# piezo-layer_v0_1-R003.net
KiCad netlist of a schematic drawn in EAGLE
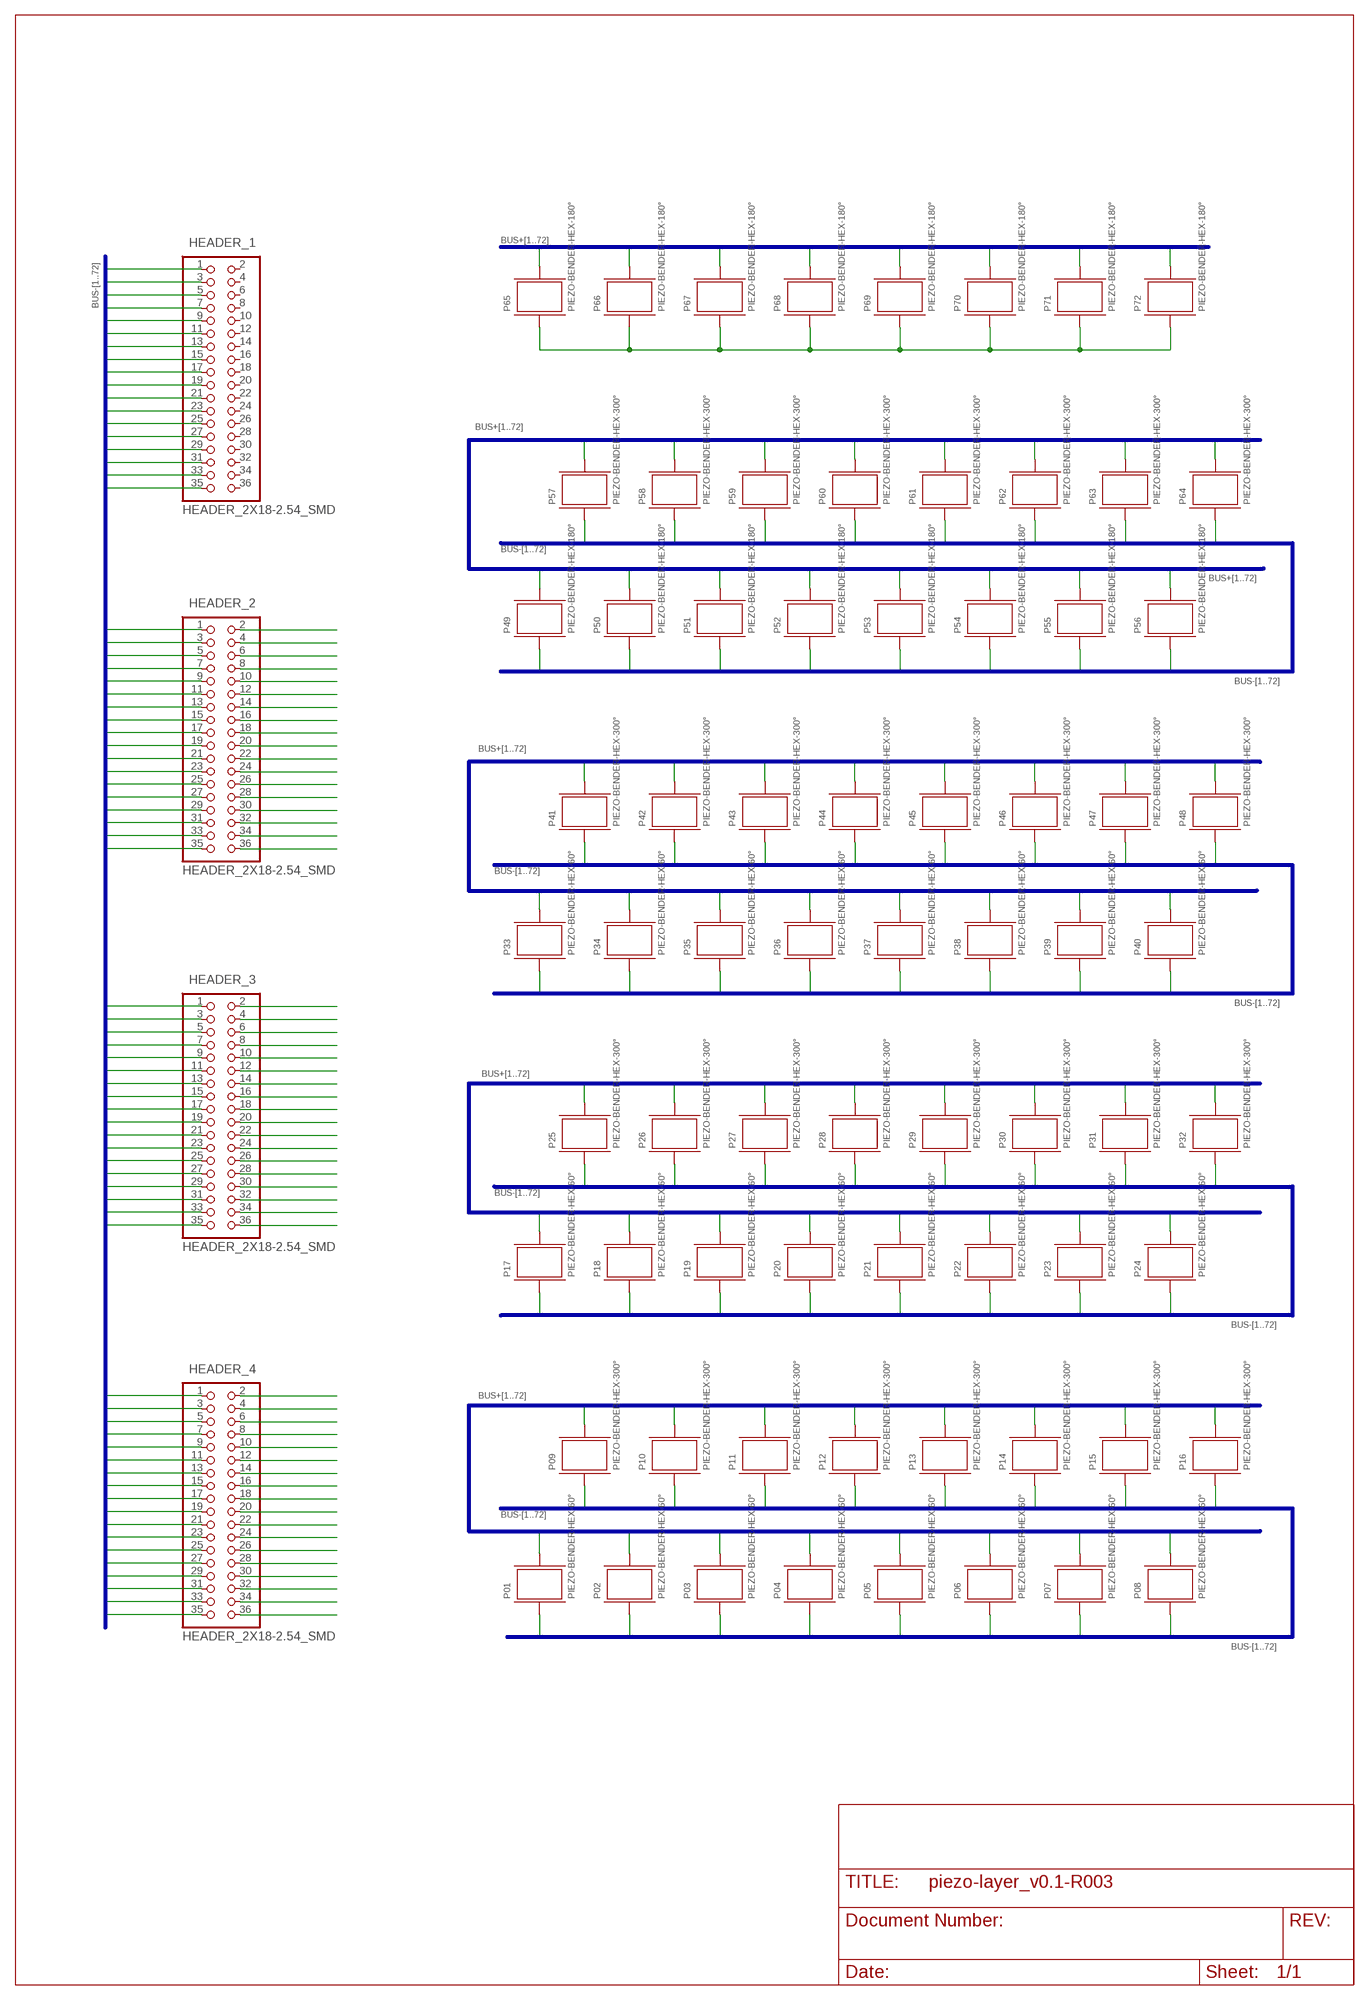
[diagram p0: schematic, sheet 1]

(export (version "E")
  (design (tool "Eeschema 10.0.6"))
  (components
    (comp (ref "HEADER_1")
      (value "HEADER_2X18-2.54_SMD")
      (footprint "eagle-import:2X18_2.54_SMD")
      (libsource (lib "eagle-import") (part "HEADER_2X18-2.54_SMD"))
    )
    (comp (ref "HEADER_2")
      (value "HEADER_2X18-2.54_SMD")
      (footprint "eagle-import:2X18_2.54_SMD")
      (libsource (lib "eagle-import") (part "HEADER_2X18-2.54_SMD"))
    )
    (comp (ref "HEADER_3")
      (value "HEADER_2X18-2.54_SMD")
      (footprint "eagle-import:2X18_2.54_SMD")
      (libsource (lib "eagle-import") (part "HEADER_2X18-2.54_SMD"))
    )
    (comp (ref "HEADER_4")
      (value "HEADER_2X18-2.54_SMD")
      (footprint "eagle-import:2X18_2.54_SMD")
      (libsource (lib "eagle-import") (part "HEADER_2X18-2.54_SMD"))
    )
    (comp (ref "P01")
      (value "PIEZO-BENDER-HEX-60°")
      (footprint "eagle-import:PIEZO-BENDER-HEX_16MM_60°")
      (libsource (lib "eagle-import") (part "PIEZO-BENDER-HEX-60°"))
    )
    (comp (ref "P02")
      (value "PIEZO-BENDER-HEX-60°")
      (footprint "eagle-import:PIEZO-BENDER-HEX_16MM_60°")
      (libsource (lib "eagle-import") (part "PIEZO-BENDER-HEX-60°"))
    )
    (comp (ref "P03")
      (value "PIEZO-BENDER-HEX-60°")
      (footprint "eagle-import:PIEZO-BENDER-HEX_16MM_60°")
      (libsource (lib "eagle-import") (part "PIEZO-BENDER-HEX-60°"))
    )
    (comp (ref "P04")
      (value "PIEZO-BENDER-HEX-60°")
      (footprint "eagle-import:PIEZO-BENDER-HEX_16MM_60°")
      (libsource (lib "eagle-import") (part "PIEZO-BENDER-HEX-60°"))
    )
    (comp (ref "P05")
      (value "PIEZO-BENDER-HEX-60°")
      (footprint "eagle-import:PIEZO-BENDER-HEX_16MM_60°")
      (libsource (lib "eagle-import") (part "PIEZO-BENDER-HEX-60°"))
    )
    (comp (ref "P06")
      (value "PIEZO-BENDER-HEX-60°")
      (footprint "eagle-import:PIEZO-BENDER-HEX_16MM_60°")
      (libsource (lib "eagle-import") (part "PIEZO-BENDER-HEX-60°"))
    )
    (comp (ref "P07")
      (value "PIEZO-BENDER-HEX-60°")
      (footprint "eagle-import:PIEZO-BENDER-HEX_16MM_60°")
      (libsource (lib "eagle-import") (part "PIEZO-BENDER-HEX-60°"))
    )
    (comp (ref "P08")
      (value "PIEZO-BENDER-HEX-60°")
      (footprint "eagle-import:PIEZO-BENDER-HEX_16MM_60°")
      (libsource (lib "eagle-import") (part "PIEZO-BENDER-HEX-60°"))
    )
    (comp (ref "P09")
      (value "PIEZO-BENDER-HEX-300°")
      (footprint "eagle-import:PIEZO-BENDER-HEX_16MM_300°")
      (libsource (lib "eagle-import") (part "PIEZO-BENDER-HEX-300°"))
    )
    (comp (ref "P10")
      (value "PIEZO-BENDER-HEX-300°")
      (footprint "eagle-import:PIEZO-BENDER-HEX_16MM_300°")
      (libsource (lib "eagle-import") (part "PIEZO-BENDER-HEX-300°"))
    )
    (comp (ref "P11")
      (value "PIEZO-BENDER-HEX-300°")
      (footprint "eagle-import:PIEZO-BENDER-HEX_16MM_300°")
      (libsource (lib "eagle-import") (part "PIEZO-BENDER-HEX-300°"))
    )
    (comp (ref "P12")
      (value "PIEZO-BENDER-HEX-300°")
      (footprint "eagle-import:PIEZO-BENDER-HEX_16MM_300°")
      (libsource (lib "eagle-import") (part "PIEZO-BENDER-HEX-300°"))
    )
    (comp (ref "P13")
      (value "PIEZO-BENDER-HEX-300°")
      (footprint "eagle-import:PIEZO-BENDER-HEX_16MM_300°")
      (libsource (lib "eagle-import") (part "PIEZO-BENDER-HEX-300°"))
    )
    (comp (ref "P14")
      (value "PIEZO-BENDER-HEX-300°")
      (footprint "eagle-import:PIEZO-BENDER-HEX_16MM_300°")
      (libsource (lib "eagle-import") (part "PIEZO-BENDER-HEX-300°"))
    )
    (comp (ref "P15")
      (value "PIEZO-BENDER-HEX-300°")
      (footprint "eagle-import:PIEZO-BENDER-HEX_16MM_300°")
      (libsource (lib "eagle-import") (part "PIEZO-BENDER-HEX-300°"))
    )
    (comp (ref "P16")
      (value "PIEZO-BENDER-HEX-300°")
      (footprint "eagle-import:PIEZO-BENDER-HEX_16MM_300°")
      (libsource (lib "eagle-import") (part "PIEZO-BENDER-HEX-300°"))
    )
    (comp (ref "P17")
      (value "PIEZO-BENDER-HEX-60°")
      (footprint "eagle-import:PIEZO-BENDER-HEX_16MM_60°")
      (libsource (lib "eagle-import") (part "PIEZO-BENDER-HEX-60°"))
    )
    (comp (ref "P18")
      (value "PIEZO-BENDER-HEX-60°")
      (footprint "eagle-import:PIEZO-BENDER-HEX_16MM_60°")
      (libsource (lib "eagle-import") (part "PIEZO-BENDER-HEX-60°"))
    )
    (comp (ref "P19")
      (value "PIEZO-BENDER-HEX-60°")
      (footprint "eagle-import:PIEZO-BENDER-HEX_16MM_60°")
      (libsource (lib "eagle-import") (part "PIEZO-BENDER-HEX-60°"))
    )
    (comp (ref "P20")
      (value "PIEZO-BENDER-HEX-60°")
      (footprint "eagle-import:PIEZO-BENDER-HEX_16MM_60°")
      (libsource (lib "eagle-import") (part "PIEZO-BENDER-HEX-60°"))
    )
    (comp (ref "P21")
      (value "PIEZO-BENDER-HEX-60°")
      (footprint "eagle-import:PIEZO-BENDER-HEX_16MM_60°")
      (libsource (lib "eagle-import") (part "PIEZO-BENDER-HEX-60°"))
    )
    (comp (ref "P22")
      (value "PIEZO-BENDER-HEX-60°")
      (footprint "eagle-import:PIEZO-BENDER-HEX_16MM_60°")
      (libsource (lib "eagle-import") (part "PIEZO-BENDER-HEX-60°"))
    )
    (comp (ref "P23")
      (value "PIEZO-BENDER-HEX-60°")
      (footprint "eagle-import:PIEZO-BENDER-HEX_16MM_60°")
      (libsource (lib "eagle-import") (part "PIEZO-BENDER-HEX-60°"))
    )
    (comp (ref "P24")
      (value "PIEZO-BENDER-HEX-60°")
      (footprint "eagle-import:PIEZO-BENDER-HEX_16MM_60°")
      (libsource (lib "eagle-import") (part "PIEZO-BENDER-HEX-60°"))
    )
    (comp (ref "P25")
      (value "PIEZO-BENDER-HEX-300°")
      (footprint "eagle-import:PIEZO-BENDER-HEX_16MM_300°")
      (libsource (lib "eagle-import") (part "PIEZO-BENDER-HEX-300°"))
    )
    (comp (ref "P26")
      (value "PIEZO-BENDER-HEX-300°")
      (footprint "eagle-import:PIEZO-BENDER-HEX_16MM_300°")
      (libsource (lib "eagle-import") (part "PIEZO-BENDER-HEX-300°"))
    )
    (comp (ref "P27")
      (value "PIEZO-BENDER-HEX-300°")
      (footprint "eagle-import:PIEZO-BENDER-HEX_16MM_300°")
      (libsource (lib "eagle-import") (part "PIEZO-BENDER-HEX-300°"))
    )
    (comp (ref "P28")
      (value "PIEZO-BENDER-HEX-300°")
      (footprint "eagle-import:PIEZO-BENDER-HEX_16MM_300°")
      (libsource (lib "eagle-import") (part "PIEZO-BENDER-HEX-300°"))
    )
    (comp (ref "P29")
      (value "PIEZO-BENDER-HEX-300°")
      (footprint "eagle-import:PIEZO-BENDER-HEX_16MM_300°")
      (libsource (lib "eagle-import") (part "PIEZO-BENDER-HEX-300°"))
    )
    (comp (ref "P30")
      (value "PIEZO-BENDER-HEX-300°")
      (footprint "eagle-import:PIEZO-BENDER-HEX_16MM_300°")
      (libsource (lib "eagle-import") (part "PIEZO-BENDER-HEX-300°"))
    )
    (comp (ref "P31")
      (value "PIEZO-BENDER-HEX-300°")
      (footprint "eagle-import:PIEZO-BENDER-HEX_16MM_300°")
      (libsource (lib "eagle-import") (part "PIEZO-BENDER-HEX-300°"))
    )
    (comp (ref "P32")
      (value "PIEZO-BENDER-HEX-300°")
      (footprint "eagle-import:PIEZO-BENDER-HEX_16MM_300°")
      (libsource (lib "eagle-import") (part "PIEZO-BENDER-HEX-300°"))
    )
    (comp (ref "P33")
      (value "PIEZO-BENDER-HEX-60°")
      (footprint "eagle-import:PIEZO-BENDER-HEX_16MM_60°")
      (libsource (lib "eagle-import") (part "PIEZO-BENDER-HEX-60°"))
    )
    (comp (ref "P34")
      (value "PIEZO-BENDER-HEX-60°")
      (footprint "eagle-import:PIEZO-BENDER-HEX_16MM_60°")
      (libsource (lib "eagle-import") (part "PIEZO-BENDER-HEX-60°"))
    )
    (comp (ref "P35")
      (value "PIEZO-BENDER-HEX-60°")
      (footprint "eagle-import:PIEZO-BENDER-HEX_16MM_60°")
      (libsource (lib "eagle-import") (part "PIEZO-BENDER-HEX-60°"))
    )
    (comp (ref "P36")
      (value "PIEZO-BENDER-HEX-60°")
      (footprint "eagle-import:PIEZO-BENDER-HEX_16MM_60°")
      (libsource (lib "eagle-import") (part "PIEZO-BENDER-HEX-60°"))
    )
    (comp (ref "P37")
      (value "PIEZO-BENDER-HEX-60°")
      (footprint "eagle-import:PIEZO-BENDER-HEX_16MM_60°")
      (libsource (lib "eagle-import") (part "PIEZO-BENDER-HEX-60°"))
    )
    (comp (ref "P38")
      (value "PIEZO-BENDER-HEX-60°")
      (footprint "eagle-import:PIEZO-BENDER-HEX_16MM_60°")
      (libsource (lib "eagle-import") (part "PIEZO-BENDER-HEX-60°"))
    )
    (comp (ref "P39")
      (value "PIEZO-BENDER-HEX-60°")
      (footprint "eagle-import:PIEZO-BENDER-HEX_16MM_60°")
      (libsource (lib "eagle-import") (part "PIEZO-BENDER-HEX-60°"))
    )
    (comp (ref "P40")
      (value "PIEZO-BENDER-HEX-60°")
      (footprint "eagle-import:PIEZO-BENDER-HEX_16MM_60°")
      (libsource (lib "eagle-import") (part "PIEZO-BENDER-HEX-60°"))
    )
    (comp (ref "P41")
      (value "PIEZO-BENDER-HEX-300°")
      (footprint "eagle-import:PIEZO-BENDER-HEX_16MM_300°")
      (libsource (lib "eagle-import") (part "PIEZO-BENDER-HEX-300°"))
    )
    (comp (ref "P42")
      (value "PIEZO-BENDER-HEX-300°")
      (footprint "eagle-import:PIEZO-BENDER-HEX_16MM_300°")
      (libsource (lib "eagle-import") (part "PIEZO-BENDER-HEX-300°"))
    )
    (comp (ref "P43")
      (value "PIEZO-BENDER-HEX-300°")
      (footprint "eagle-import:PIEZO-BENDER-HEX_16MM_300°")
      (libsource (lib "eagle-import") (part "PIEZO-BENDER-HEX-300°"))
    )
    (comp (ref "P44")
      (value "PIEZO-BENDER-HEX-300°")
      (footprint "eagle-import:PIEZO-BENDER-HEX_16MM_300°")
      (libsource (lib "eagle-import") (part "PIEZO-BENDER-HEX-300°"))
    )
    (comp (ref "P45")
      (value "PIEZO-BENDER-HEX-300°")
      (footprint "eagle-import:PIEZO-BENDER-HEX_16MM_300°")
      (libsource (lib "eagle-import") (part "PIEZO-BENDER-HEX-300°"))
    )
    (comp (ref "P46")
      (value "PIEZO-BENDER-HEX-300°")
      (footprint "eagle-import:PIEZO-BENDER-HEX_16MM_300°")
      (libsource (lib "eagle-import") (part "PIEZO-BENDER-HEX-300°"))
    )
    (comp (ref "P47")
      (value "PIEZO-BENDER-HEX-300°")
      (footprint "eagle-import:PIEZO-BENDER-HEX_16MM_300°")
      (libsource (lib "eagle-import") (part "PIEZO-BENDER-HEX-300°"))
    )
    (comp (ref "P48")
      (value "PIEZO-BENDER-HEX-300°")
      (footprint "eagle-import:PIEZO-BENDER-HEX_16MM_300°")
      (libsource (lib "eagle-import") (part "PIEZO-BENDER-HEX-300°"))
    )
    (comp (ref "P49")
      (value "PIEZO-BENDER-HEX-180°")
      (footprint "eagle-import:PIEZO-BENDER-HEX_16MM_180°")
      (libsource (lib "eagle-import") (part "PIEZO-BENDER-HEX-180°"))
    )
    (comp (ref "P50")
      (value "PIEZO-BENDER-HEX-180°")
      (footprint "eagle-import:PIEZO-BENDER-HEX_16MM_180°")
      (libsource (lib "eagle-import") (part "PIEZO-BENDER-HEX-180°"))
    )
    (comp (ref "P51")
      (value "PIEZO-BENDER-HEX-180°")
      (footprint "eagle-import:PIEZO-BENDER-HEX_16MM_180°")
      (libsource (lib "eagle-import") (part "PIEZO-BENDER-HEX-180°"))
    )
    (comp (ref "P52")
      (value "PIEZO-BENDER-HEX-180°")
      (footprint "eagle-import:PIEZO-BENDER-HEX_16MM_180°")
      (libsource (lib "eagle-import") (part "PIEZO-BENDER-HEX-180°"))
    )
    (comp (ref "P53")
      (value "PIEZO-BENDER-HEX-180°")
      (footprint "eagle-import:PIEZO-BENDER-HEX_16MM_180°")
      (libsource (lib "eagle-import") (part "PIEZO-BENDER-HEX-180°"))
    )
    (comp (ref "P54")
      (value "PIEZO-BENDER-HEX-180°")
      (footprint "eagle-import:PIEZO-BENDER-HEX_16MM_180°")
      (libsource (lib "eagle-import") (part "PIEZO-BENDER-HEX-180°"))
    )
    (comp (ref "P55")
      (value "PIEZO-BENDER-HEX-180°")
      (footprint "eagle-import:PIEZO-BENDER-HEX_16MM_180°")
      (libsource (lib "eagle-import") (part "PIEZO-BENDER-HEX-180°"))
    )
    (comp (ref "P56")
      (value "PIEZO-BENDER-HEX-180°")
      (footprint "eagle-import:PIEZO-BENDER-HEX_16MM_180°")
      (libsource (lib "eagle-import") (part "PIEZO-BENDER-HEX-180°"))
    )
    (comp (ref "P57")
      (value "PIEZO-BENDER-HEX-300°")
      (footprint "eagle-import:PIEZO-BENDER-HEX_16MM_300°")
      (libsource (lib "eagle-import") (part "PIEZO-BENDER-HEX-300°"))
    )
    (comp (ref "P58")
      (value "PIEZO-BENDER-HEX-300°")
      (footprint "eagle-import:PIEZO-BENDER-HEX_16MM_300°")
      (libsource (lib "eagle-import") (part "PIEZO-BENDER-HEX-300°"))
    )
    (comp (ref "P59")
      (value "PIEZO-BENDER-HEX-300°")
      (footprint "eagle-import:PIEZO-BENDER-HEX_16MM_300°")
      (libsource (lib "eagle-import") (part "PIEZO-BENDER-HEX-300°"))
    )
    (comp (ref "P60")
      (value "PIEZO-BENDER-HEX-300°")
      (footprint "eagle-import:PIEZO-BENDER-HEX_16MM_300°")
      (libsource (lib "eagle-import") (part "PIEZO-BENDER-HEX-300°"))
    )
    (comp (ref "P61")
      (value "PIEZO-BENDER-HEX-300°")
      (footprint "eagle-import:PIEZO-BENDER-HEX_16MM_300°")
      (libsource (lib "eagle-import") (part "PIEZO-BENDER-HEX-300°"))
    )
    (comp (ref "P62")
      (value "PIEZO-BENDER-HEX-300°")
      (footprint "eagle-import:PIEZO-BENDER-HEX_16MM_300°")
      (libsource (lib "eagle-import") (part "PIEZO-BENDER-HEX-300°"))
    )
    (comp (ref "P63")
      (value "PIEZO-BENDER-HEX-300°")
      (footprint "eagle-import:PIEZO-BENDER-HEX_16MM_300°")
      (libsource (lib "eagle-import") (part "PIEZO-BENDER-HEX-300°"))
    )
    (comp (ref "P64")
      (value "PIEZO-BENDER-HEX-300°")
      (footprint "eagle-import:PIEZO-BENDER-HEX_16MM_300°")
      (libsource (lib "eagle-import") (part "PIEZO-BENDER-HEX-300°"))
    )
    (comp (ref "P65")
      (value "PIEZO-BENDER-HEX-180°")
      (footprint "eagle-import:PIEZO-BENDER-HEX_16MM_180°")
      (libsource (lib "eagle-import") (part "PIEZO-BENDER-HEX-180°"))
    )
    (comp (ref "P66")
      (value "PIEZO-BENDER-HEX-180°")
      (footprint "eagle-import:PIEZO-BENDER-HEX_16MM_180°")
      (libsource (lib "eagle-import") (part "PIEZO-BENDER-HEX-180°"))
    )
    (comp (ref "P67")
      (value "PIEZO-BENDER-HEX-180°")
      (footprint "eagle-import:PIEZO-BENDER-HEX_16MM_180°")
      (libsource (lib "eagle-import") (part "PIEZO-BENDER-HEX-180°"))
    )
    (comp (ref "P68")
      (value "PIEZO-BENDER-HEX-180°")
      (footprint "eagle-import:PIEZO-BENDER-HEX_16MM_180°")
      (libsource (lib "eagle-import") (part "PIEZO-BENDER-HEX-180°"))
    )
    (comp (ref "P69")
      (value "PIEZO-BENDER-HEX-180°")
      (footprint "eagle-import:PIEZO-BENDER-HEX_16MM_180°")
      (libsource (lib "eagle-import") (part "PIEZO-BENDER-HEX-180°"))
    )
    (comp (ref "P70")
      (value "PIEZO-BENDER-HEX-180°")
      (footprint "eagle-import:PIEZO-BENDER-HEX_16MM_180°")
      (libsource (lib "eagle-import") (part "PIEZO-BENDER-HEX-180°"))
    )
    (comp (ref "P71")
      (value "PIEZO-BENDER-HEX-180°")
      (footprint "eagle-import:PIEZO-BENDER-HEX_16MM_180°")
      (libsource (lib "eagle-import") (part "PIEZO-BENDER-HEX-180°"))
    )
    (comp (ref "P72")
      (value "PIEZO-BENDER-HEX-180°")
      (footprint "eagle-import:PIEZO-BENDER-HEX_16MM_180°")
      (libsource (lib "eagle-import") (part "PIEZO-BENDER-HEX-180°"))
    )
  )
  (nets
    (net (code "26") (name "/BUS+3") (class "Default")
      (node (ref "HEADER_2") (pin "18") (pinfunction "18_18") (pintype "passive"))
      (node (ref "P03") (pin "TIP1") (pinfunction "+_1_TIP1") (pintype "bidirectional"))
    )
    (net (code "27") (name "/BUS+4") (class "Default")
      (node (ref "HEADER_2") (pin "36") (pinfunction "36_36") (pintype "passive"))
      (node (ref "P04") (pin "TIP1") (pinfunction "+_1_TIP1") (pintype "bidirectional"))
    )
    (net (code "28") (name "/BUS+5") (class "Default")
      (node (ref "HEADER_3") (pin "18") (pinfunction "18_18") (pintype "passive"))
      (node (ref "P05") (pin "TIP1") (pinfunction "+_1_TIP1") (pintype "bidirectional"))
    )
    (net (code "29") (name "/BUS+6") (class "Default")
      (node (ref "HEADER_3") (pin "36") (pinfunction "36_36") (pintype "passive"))
      (node (ref "P06") (pin "TIP1") (pinfunction "+_1_TIP1") (pintype "bidirectional"))
    )
    (net (code "30") (name "/BUS+7") (class "Default")
      (node (ref "HEADER_4") (pin "18") (pinfunction "18_18") (pintype "passive"))
      (node (ref "P07") (pin "TIP1") (pinfunction "+_1_TIP1") (pintype "bidirectional"))
    )
    (net (code "31") (name "/BUS+8") (class "Default")
      (node (ref "HEADER_4") (pin "36") (pinfunction "36_36") (pintype "passive"))
      (node (ref "P08") (pin "TIP1") (pinfunction "+_1_TIP1") (pintype "bidirectional"))
    )
    (net (code "32") (name "/BUS+11") (class "Default")
      (node (ref "HEADER_2") (pin "16") (pinfunction "16_16") (pintype "passive"))
      (node (ref "P11") (pin "TIP1") (pinfunction "+_1_TIP1") (pintype "bidirectional"))
    )
    (net (code "33") (name "/BUS+12") (class "Default")
      (node (ref "HEADER_2") (pin "34") (pinfunction "34_34") (pintype "passive"))
      (node (ref "P12") (pin "TIP1") (pinfunction "+_1_TIP1") (pintype "bidirectional"))
    )
    (net (code "34") (name "/BUS+13") (class "Default")
      (node (ref "HEADER_3") (pin "16") (pinfunction "16_16") (pintype "passive"))
      (node (ref "P13") (pin "TIP1") (pinfunction "+_1_TIP1") (pintype "bidirectional"))
    )
    (net (code "35") (name "/BUS+14") (class "Default")
      (node (ref "HEADER_3") (pin "34") (pinfunction "34_34") (pintype "passive"))
      (node (ref "P14") (pin "TIP1") (pinfunction "+_1_TIP1") (pintype "bidirectional"))
    )
    (net (code "36") (name "/BUS+15") (class "Default")
      (node (ref "HEADER_4") (pin "16") (pinfunction "16_16") (pintype "passive"))
      (node (ref "P15") (pin "TIP1") (pinfunction "+_1_TIP1") (pintype "bidirectional"))
    )
    (net (code "37") (name "/BUS+16") (class "Default")
      (node (ref "HEADER_4") (pin "34") (pinfunction "34_34") (pintype "passive"))
      (node (ref "P16") (pin "TIP1") (pinfunction "+_1_TIP1") (pintype "bidirectional"))
    )
    (net (code "38") (name "/BUS+19") (class "Default")
      (node (ref "HEADER_2") (pin "14") (pinfunction "14_14") (pintype "passive"))
      (node (ref "P19") (pin "TIP1") (pinfunction "+_1_TIP1") (pintype "bidirectional"))
    )
    (net (code "39") (name "/BUS+20") (class "Default")
      (node (ref "HEADER_2") (pin "32") (pinfunction "32_32") (pintype "passive"))
      (node (ref "P20") (pin "TIP1") (pinfunction "+_1_TIP1") (pintype "bidirectional"))
    )
    (net (code "40") (name "/BUS+21") (class "Default")
      (node (ref "HEADER_3") (pin "14") (pinfunction "14_14") (pintype "passive"))
      (node (ref "P21") (pin "TIP1") (pinfunction "+_1_TIP1") (pintype "bidirectional"))
    )
    (net (code "41") (name "/BUS+22") (class "Default")
      (node (ref "HEADER_3") (pin "32") (pinfunction "32_32") (pintype "passive"))
      (node (ref "P22") (pin "TIP1") (pinfunction "+_1_TIP1") (pintype "bidirectional"))
    )
    (net (code "42") (name "/BUS+23") (class "Default")
      (node (ref "HEADER_4") (pin "14") (pinfunction "14_14") (pintype "passive"))
      (node (ref "P23") (pin "TIP1") (pinfunction "+_1_TIP1") (pintype "bidirectional"))
    )
    (net (code "43") (name "/BUS+24") (class "Default")
      (node (ref "HEADER_4") (pin "32") (pinfunction "32_32") (pintype "passive"))
      (node (ref "P24") (pin "TIP1") (pinfunction "+_1_TIP1") (pintype "bidirectional"))
    )
    (net (code "44") (name "/BUS+27") (class "Default")
      (node (ref "HEADER_2") (pin "12") (pinfunction "12_12") (pintype "passive"))
      (node (ref "P27") (pin "TIP1") (pinfunction "+_1_TIP1") (pintype "bidirectional"))
    )
    (net (code "45") (name "/BUS+28") (class "Default")
      (node (ref "HEADER_2") (pin "30") (pinfunction "30_30") (pintype "passive"))
      (node (ref "P28") (pin "TIP1") (pinfunction "+_1_TIP1") (pintype "bidirectional"))
    )
    (net (code "46") (name "/BUS+29") (class "Default")
      (node (ref "HEADER_3") (pin "12") (pinfunction "12_12") (pintype "passive"))
      (node (ref "P29") (pin "TIP1") (pinfunction "+_1_TIP1") (pintype "bidirectional"))
    )
    (net (code "47") (name "/BUS+30") (class "Default")
      (node (ref "HEADER_3") (pin "30") (pinfunction "30_30") (pintype "passive"))
      (node (ref "P30") (pin "TIP1") (pinfunction "+_1_TIP1") (pintype "bidirectional"))
    )
    (net (code "48") (name "/BUS+31") (class "Default")
      (node (ref "HEADER_4") (pin "12") (pinfunction "12_12") (pintype "passive"))
      (node (ref "P31") (pin "TIP1") (pinfunction "+_1_TIP1") (pintype "bidirectional"))
    )
    (net (code "49") (name "/BUS+32") (class "Default")
      (node (ref "HEADER_4") (pin "30") (pinfunction "30_30") (pintype "passive"))
      (node (ref "P32") (pin "TIP1") (pinfunction "+_1_TIP1") (pintype "bidirectional"))
    )
    (net (code "50") (name "/BUS+35") (class "Default")
      (node (ref "HEADER_2") (pin "10") (pinfunction "10_10") (pintype "passive"))
      (node (ref "P35") (pin "TIP1") (pinfunction "+_1_TIP1") (pintype "bidirectional"))
    )
    (net (code "51") (name "/BUS+36") (class "Default")
      (node (ref "HEADER_2") (pin "28") (pinfunction "28_28") (pintype "passive"))
      (node (ref "P36") (pin "TIP1") (pinfunction "+_1_TIP1") (pintype "bidirectional"))
    )
    (net (code "52") (name "/BUS+37") (class "Default")
      (node (ref "HEADER_3") (pin "10") (pinfunction "10_10") (pintype "passive"))
      (node (ref "P37") (pin "TIP1") (pinfunction "+_1_TIP1") (pintype "bidirectional"))
    )
    (net (code "53") (name "/BUS+38") (class "Default")
      (node (ref "HEADER_3") (pin "28") (pinfunction "28_28") (pintype "passive"))
      (node (ref "P38") (pin "TIP1") (pinfunction "+_1_TIP1") (pintype "bidirectional"))
    )
    (net (code "54") (name "/BUS+39") (class "Default")
      (node (ref "HEADER_4") (pin "10") (pinfunction "10_10") (pintype "passive"))
      (node (ref "P39") (pin "TIP1") (pinfunction "+_1_TIP1") (pintype "bidirectional"))
    )
    (net (code "55") (name "/BUS+40") (class "Default")
      (node (ref "HEADER_4") (pin "28") (pinfunction "28_28") (pintype "passive"))
      (node (ref "P40") (pin "TIP1") (pinfunction "+_1_TIP1") (pintype "bidirectional"))
    )
    (net (code "56") (name "/BUS+43") (class "Default")
      (node (ref "HEADER_2") (pin "8") (pinfunction "8_8") (pintype "passive"))
      (node (ref "P43") (pin "TIP1") (pinfunction "+_1_TIP1") (pintype "bidirectional"))
    )
    (net (code "57") (name "/BUS+44") (class "Default")
      (node (ref "HEADER_2") (pin "26") (pinfunction "26_26") (pintype "passive"))
      (node (ref "P44") (pin "TIP1") (pinfunction "+_1_TIP1") (pintype "bidirectional"))
    )
    (net (code "58") (name "/BUS+45") (class "Default")
      (node (ref "HEADER_3") (pin "8") (pinfunction "8_8") (pintype "passive"))
      (node (ref "P45") (pin "TIP1") (pinfunction "+_1_TIP1") (pintype "bidirectional"))
    )
    (net (code "59") (name "/BUS+46") (class "Default")
      (node (ref "HEADER_3") (pin "26") (pinfunction "26_26") (pintype "passive"))
      (node (ref "P46") (pin "TIP1") (pinfunction "+_1_TIP1") (pintype "bidirectional"))
    )
    (net (code "60") (name "/BUS+47") (class "Default")
      (node (ref "HEADER_4") (pin "8") (pinfunction "8_8") (pintype "passive"))
      (node (ref "P47") (pin "TIP1") (pinfunction "+_1_TIP1") (pintype "bidirectional"))
    )
    (net (code "61") (name "/BUS+48") (class "Default")
      (node (ref "HEADER_4") (pin "26") (pinfunction "26_26") (pintype "passive"))
      (node (ref "P48") (pin "TIP1") (pinfunction "+_1_TIP1") (pintype "bidirectional"))
    )
    (net (code "62") (name "/BUS+51") (class "Default")
      (node (ref "HEADER_2") (pin "6") (pinfunction "6_6") (pintype "passive"))
      (node (ref "P51") (pin "TIP1") (pinfunction "+_1_TIP1") (pintype "bidirectional"))
    )
    (net (code "63") (name "/BUS+52") (class "Default")
      (node (ref "HEADER_2") (pin "24") (pinfunction "24_24") (pintype "passive"))
      (node (ref "P52") (pin "TIP1") (pinfunction "+_1_TIP1") (pintype "bidirectional"))
    )
    (net (code "64") (name "/BUS+53") (class "Default")
      (node (ref "HEADER_3") (pin "6") (pinfunction "6_6") (pintype "passive"))
      (node (ref "P53") (pin "TIP1") (pinfunction "+_1_TIP1") (pintype "bidirectional"))
    )
    (net (code "65") (name "/BUS+54") (class "Default")
      (node (ref "HEADER_3") (pin "24") (pinfunction "24_24") (pintype "passive"))
      (node (ref "P54") (pin "TIP1") (pinfunction "+_1_TIP1") (pintype "bidirectional"))
    )
    (net (code "66") (name "/BUS+55") (class "Default")
      (node (ref "HEADER_4") (pin "6") (pinfunction "6_6") (pintype "passive"))
      (node (ref "P55") (pin "TIP1") (pinfunction "+_1_TIP1") (pintype "bidirectional"))
    )
    (net (code "67") (name "/BUS+56") (class "Default")
      (node (ref "HEADER_4") (pin "24") (pinfunction "24_24") (pintype "passive"))
      (node (ref "P56") (pin "TIP1") (pinfunction "+_1_TIP1") (pintype "bidirectional"))
    )
    (net (code "68") (name "/BUS+59") (class "Default")
      (node (ref "HEADER_2") (pin "4") (pinfunction "4_4") (pintype "passive"))
      (node (ref "P59") (pin "TIP1") (pinfunction "+_1_TIP1") (pintype "bidirectional"))
    )
    (net (code "69") (name "/BUS+60") (class "Default")
      (node (ref "HEADER_2") (pin "22") (pinfunction "22_22") (pintype "passive"))
      (node (ref "P60") (pin "TIP1") (pinfunction "+_1_TIP1") (pintype "bidirectional"))
    )
    (net (code "70") (name "/BUS+61") (class "Default")
      (node (ref "HEADER_3") (pin "4") (pinfunction "4_4") (pintype "passive"))
      (node (ref "P61") (pin "TIP1") (pinfunction "+_1_TIP1") (pintype "bidirectional"))
    )
    (net (code "71") (name "/BUS+62") (class "Default")
      (node (ref "HEADER_3") (pin "22") (pinfunction "22_22") (pintype "passive"))
      (node (ref "P62") (pin "TIP1") (pinfunction "+_1_TIP1") (pintype "bidirectional"))
    )
    (net (code "72") (name "/BUS+63") (class "Default")
      (node (ref "HEADER_4") (pin "4") (pinfunction "4_4") (pintype "passive"))
      (node (ref "P63") (pin "TIP1") (pinfunction "+_1_TIP1") (pintype "bidirectional"))
    )
    (net (code "73") (name "/BUS+64") (class "Default")
      (node (ref "HEADER_4") (pin "22") (pinfunction "22_22") (pintype "passive"))
      (node (ref "P64") (pin "TIP1") (pinfunction "+_1_TIP1") (pintype "bidirectional"))
    )
    (net (code "74") (name "/BUS+67") (class "Default")
      (node (ref "HEADER_2") (pin "2") (pinfunction "2_2") (pintype "passive"))
      (node (ref "P67") (pin "TIP1") (pinfunction "+_1_TIP1") (pintype "bidirectional"))
    )
    (net (code "75") (name "/BUS+68") (class "Default")
      (node (ref "HEADER_2") (pin "20") (pinfunction "20_20") (pintype "passive"))
      (node (ref "P68") (pin "TIP1") (pinfunction "+_1_TIP1") (pintype "bidirectional"))
    )
    (net (code "76") (name "/BUS+69") (class "Default")
      (node (ref "HEADER_3") (pin "2") (pinfunction "2_2") (pintype "passive"))
      (node (ref "P69") (pin "TIP1") (pinfunction "+_1_TIP1") (pintype "bidirectional"))
    )
    (net (code "77") (name "/BUS+70") (class "Default")
      (node (ref "HEADER_3") (pin "20") (pinfunction "20_20") (pintype "passive"))
      (node (ref "P70") (pin "TIP1") (pinfunction "+_1_TIP1") (pintype "bidirectional"))
    )
    (net (code "78") (name "/BUS+71") (class "Default")
      (node (ref "HEADER_4") (pin "2") (pinfunction "2_2") (pintype "passive"))
      (node (ref "P71") (pin "TIP1") (pinfunction "+_1_TIP1") (pintype "bidirectional"))
    )
    (net (code "79") (name "/BUS+72") (class "Default")
      (node (ref "HEADER_4") (pin "20") (pinfunction "20_20") (pintype "passive"))
      (node (ref "P72") (pin "TIP1") (pinfunction "+_1_TIP1") (pintype "bidirectional"))
    )
    (net (code "81") (name "/BUS-1") (class "Default")
      (node (ref "HEADER_1") (pin "17") (pinfunction "17_17") (pintype "passive"))
      (node (ref "P01") (pin "PAD1") (pinfunction "-_1_PAD1") (pintype "bidirectional"))
    )
    (net (code "82") (name "/BUS-2") (class "Default")
      (node (ref "HEADER_1") (pin "35") (pinfunction "35_35") (pintype "passive"))
      (node (ref "P02") (pin "PAD1") (pinfunction "-_1_PAD1") (pintype "bidirectional"))
    )
    (net (code "83") (name "/BUS-3") (class "Default")
      (node (ref "HEADER_2") (pin "17") (pinfunction "17_17") (pintype "passive"))
      (node (ref "P03") (pin "PAD1") (pinfunction "-_1_PAD1") (pintype "bidirectional"))
    )
    (net (code "84") (name "/BUS-4") (class "Default")
      (node (ref "HEADER_2") (pin "35") (pinfunction "35_35") (pintype "passive"))
      (node (ref "P04") (pin "PAD1") (pinfunction "-_1_PAD1") (pintype "bidirectional"))
    )
    (net (code "85") (name "/BUS-5") (class "Default")
      (node (ref "HEADER_3") (pin "17") (pinfunction "17_17") (pintype "passive"))
      (node (ref "P05") (pin "PAD1") (pinfunction "-_1_PAD1") (pintype "bidirectional"))
    )
    (net (code "86") (name "/BUS-6") (class "Default")
      (node (ref "HEADER_3") (pin "35") (pinfunction "35_35") (pintype "passive"))
      (node (ref "P06") (pin "PAD1") (pinfunction "-_1_PAD1") (pintype "bidirectional"))
    )
    (net (code "87") (name "/BUS-7") (class "Default")
      (node (ref "HEADER_4") (pin "17") (pinfunction "17_17") (pintype "passive"))
      (node (ref "P07") (pin "PAD1") (pinfunction "-_1_PAD1") (pintype "bidirectional"))
    )
    (net (code "88") (name "/BUS-8") (class "Default")
      (node (ref "HEADER_4") (pin "35") (pinfunction "35_35") (pintype "passive"))
      (node (ref "P08") (pin "PAD1") (pinfunction "-_1_PAD1") (pintype "bidirectional"))
    )
    (net (code "89") (name "/BUS-9") (class "Default")
      (node (ref "HEADER_1") (pin "15") (pinfunction "15_15") (pintype "passive"))
      (node (ref "P09") (pin "PAD1") (pinfunction "-_1_PAD1") (pintype "bidirectional"))
    )
    (net (code "90") (name "/BUS-10") (class "Default")
      (node (ref "HEADER_1") (pin "33") (pinfunction "33_33") (pintype "passive"))
      (node (ref "P10") (pin "PAD1") (pinfunction "-_1_PAD1") (pintype "bidirectional"))
    )
    (net (code "91") (name "/BUS-11") (class "Default")
      (node (ref "HEADER_2") (pin "15") (pinfunction "15_15") (pintype "passive"))
      (node (ref "P11") (pin "PAD1") (pinfunction "-_1_PAD1") (pintype "bidirectional"))
    )
    (net (code "92") (name "/BUS-12") (class "Default")
      (node (ref "HEADER_2") (pin "33") (pinfunction "33_33") (pintype "passive"))
      (node (ref "P12") (pin "PAD1") (pinfunction "-_1_PAD1") (pintype "bidirectional"))
    )
    (net (code "93") (name "/BUS-13") (class "Default")
      (node (ref "HEADER_3") (pin "15") (pinfunction "15_15") (pintype "passive"))
      (node (ref "P13") (pin "PAD1") (pinfunction "-_1_PAD1") (pintype "bidirectional"))
    )
    (net (code "94") (name "/BUS-14") (class "Default")
      (node (ref "HEADER_3") (pin "33") (pinfunction "33_33") (pintype "passive"))
      (node (ref "P14") (pin "PAD1") (pinfunction "-_1_PAD1") (pintype "bidirectional"))
    )
    (net (code "95") (name "/BUS-15") (class "Default")
      (node (ref "HEADER_4") (pin "15") (pinfunction "15_15") (pintype "passive"))
      (node (ref "P15") (pin "PAD1") (pinfunction "-_1_PAD1") (pintype "bidirectional"))
    )
    (net (code "96") (name "/BUS-16") (class "Default")
      (node (ref "HEADER_4") (pin "33") (pinfunction "33_33") (pintype "passive"))
      (node (ref "P16") (pin "PAD1") (pinfunction "-_1_PAD1") (pintype "bidirectional"))
    )
    (net (code "97") (name "/BUS-17") (class "Default")
      (node (ref "HEADER_1") (pin "13") (pinfunction "13_13") (pintype "passive"))
      (node (ref "P17") (pin "PAD1") (pinfunction "-_1_PAD1") (pintype "bidirectional"))
    )
    (net (code "98") (name "/BUS-18") (class "Default")
      (node (ref "HEADER_1") (pin "31") (pinfunction "31_31") (pintype "passive"))
      (node (ref "P18") (pin "PAD1") (pinfunction "-_1_PAD1") (pintype "bidirectional"))
    )
    (net (code "99") (name "/BUS-19") (class "Default")
      (node (ref "HEADER_2") (pin "13") (pinfunction "13_13") (pintype "passive"))
      (node (ref "P19") (pin "PAD1") (pinfunction "-_1_PAD1") (pintype "bidirectional"))
    )
    (net (code "100") (name "/BUS-20") (class "Default")
      (node (ref "HEADER_2") (pin "31") (pinfunction "31_31") (pintype "passive"))
      (node (ref "P20") (pin "PAD1") (pinfunction "-_1_PAD1") (pintype "bidirectional"))
    )
    (net (code "101") (name "/BUS-21") (class "Default")
      (node (ref "HEADER_3") (pin "13") (pinfunction "13_13") (pintype "passive"))
      (node (ref "P21") (pin "PAD1") (pinfunction "-_1_PAD1") (pintype "bidirectional"))
    )
    (net (code "102") (name "/BUS-22") (class "Default")
      (node (ref "HEADER_3") (pin "31") (pinfunction "31_31") (pintype "passive"))
      (node (ref "P22") (pin "PAD1") (pinfunction "-_1_PAD1") (pintype "bidirectional"))
    )
    (net (code "103") (name "/BUS-23") (class "Default")
      (node (ref "HEADER_4") (pin "13") (pinfunction "13_13") (pintype "passive"))
      (node (ref "P23") (pin "PAD1") (pinfunction "-_1_PAD1") (pintype "bidirectional"))
    )
    (net (code "104") (name "/BUS-24") (class "Default")
      (node (ref "HEADER_4") (pin "31") (pinfunction "31_31") (pintype "passive"))
      (node (ref "P24") (pin "PAD1") (pinfunction "-_1_PAD1") (pintype "bidirectional"))
    )
    (net (code "105") (name "/BUS-25") (class "Default")
      (node (ref "HEADER_1") (pin "11") (pinfunction "11_11") (pintype "passive"))
      (node (ref "P25") (pin "PAD1") (pinfunction "-_1_PAD1") (pintype "bidirectional"))
    )
    (net (code "106") (name "/BUS-26") (class "Default")
      (node (ref "HEADER_1") (pin "29") (pinfunction "29_29") (pintype "passive"))
      (node (ref "P26") (pin "PAD1") (pinfunction "-_1_PAD1") (pintype "bidirectional"))
    )
    (net (code "107") (name "/BUS-27") (class "Default")
      (node (ref "HEADER_2") (pin "11") (pinfunction "11_11") (pintype "passive"))
      (node (ref "P27") (pin "PAD1") (pinfunction "-_1_PAD1") (pintype "bidirectional"))
    )
    (net (code "108") (name "/BUS-28") (class "Default")
      (node (ref "HEADER_2") (pin "29") (pinfunction "29_29") (pintype "passive"))
      (node (ref "P28") (pin "PAD1") (pinfunction "-_1_PAD1") (pintype "bidirectional"))
    )
    (net (code "109") (name "/BUS-29") (class "Default")
      (node (ref "HEADER_3") (pin "11") (pinfunction "11_11") (pintype "passive"))
      (node (ref "P29") (pin "PAD1") (pinfunction "-_1_PAD1") (pintype "bidirectional"))
    )
    (net (code "110") (name "/BUS-30") (class "Default")
      (node (ref "HEADER_3") (pin "29") (pinfunction "29_29") (pintype "passive"))
      (node (ref "P30") (pin "PAD1") (pinfunction "-_1_PAD1") (pintype "bidirectional"))
    )
    (net (code "111") (name "/BUS-31") (class "Default")
      (node (ref "HEADER_4") (pin "11") (pinfunction "11_11") (pintype "passive"))
      (node (ref "P31") (pin "PAD1") (pinfunction "-_1_PAD1") (pintype "bidirectional"))
    )
    (net (code "112") (name "/BUS-32") (class "Default")
      (node (ref "HEADER_4") (pin "29") (pinfunction "29_29") (pintype "passive"))
      (node (ref "P32") (pin "PAD1") (pinfunction "-_1_PAD1") (pintype "bidirectional"))
    )
    (net (code "113") (name "/BUS-33") (class "Default")
      (node (ref "HEADER_1") (pin "9") (pinfunction "9_9") (pintype "passive"))
      (node (ref "P33") (pin "PAD1") (pinfunction "-_1_PAD1") (pintype "bidirectional"))
    )
    (net (code "114") (name "/BUS-34") (class "Default")
      (node (ref "HEADER_1") (pin "27") (pinfunction "27_27") (pintype "passive"))
      (node (ref "P34") (pin "PAD1") (pinfunction "-_1_PAD1") (pintype "bidirectional"))
    )
    (net (code "115") (name "/BUS-35") (class "Default")
      (node (ref "HEADER_2") (pin "9") (pinfunction "9_9") (pintype "passive"))
      (node (ref "P35") (pin "PAD1") (pinfunction "-_1_PAD1") (pintype "bidirectional"))
    )
    (net (code "116") (name "/BUS-36") (class "Default")
      (node (ref "HEADER_2") (pin "27") (pinfunction "27_27") (pintype "passive"))
      (node (ref "P36") (pin "PAD1") (pinfunction "-_1_PAD1") (pintype "bidirectional"))
    )
    (net (code "117") (name "/BUS-37") (class "Default")
      (node (ref "HEADER_3") (pin "9") (pinfunction "9_9") (pintype "passive"))
      (node (ref "P37") (pin "PAD1") (pinfunction "-_1_PAD1") (pintype "bidirectional"))
    )
    (net (code "118") (name "/BUS-38") (class "Default")
      (node (ref "HEADER_3") (pin "27") (pinfunction "27_27") (pintype "passive"))
      (node (ref "P38") (pin "PAD1") (pinfunction "-_1_PAD1") (pintype "bidirectional"))
    )
    (net (code "119") (name "/BUS-39") (class "Default")
      (node (ref "HEADER_4") (pin "9") (pinfunction "9_9") (pintype "passive"))
      (node (ref "P39") (pin "PAD1") (pinfunction "-_1_PAD1") (pintype "bidirectional"))
    )
    (net (code "120") (name "/BUS-40") (class "Default")
      (node (ref "HEADER_4") (pin "27") (pinfunction "27_27") (pintype "passive"))
      (node (ref "P40") (pin "PAD1") (pinfunction "-_1_PAD1") (pintype "bidirectional"))
    )
    (net (code "121") (name "/BUS-41") (class "Default")
      (node (ref "HEADER_1") (pin "7") (pinfunction "7_7") (pintype "passive"))
      (node (ref "P41") (pin "PAD1") (pinfunction "-_1_PAD1") (pintype "bidirectional"))
    )
    (net (code "122") (name "/BUS-42") (class "Default")
      (node (ref "HEADER_1") (pin "25") (pinfunction "25_25") (pintype "passive"))
      (node (ref "P42") (pin "PAD1") (pinfunction "-_1_PAD1") (pintype "bidirectional"))
    )
    (net (code "123") (name "/BUS-43") (class "Default")
      (node (ref "HEADER_2") (pin "7") (pinfunction "7_7") (pintype "passive"))
      (node (ref "P43") (pin "PAD1") (pinfunction "-_1_PAD1") (pintype "bidirectional"))
    )
    (net (code "124") (name "/BUS-44") (class "Default")
      (node (ref "HEADER_2") (pin "25") (pinfunction "25_25") (pintype "passive"))
      (node (ref "P44") (pin "PAD1") (pinfunction "-_1_PAD1") (pintype "bidirectional"))
    )
    (net (code "125") (name "/BUS-45") (class "Default")
      (node (ref "HEADER_3") (pin "7") (pinfunction "7_7") (pintype "passive"))
      (node (ref "P45") (pin "PAD1") (pinfunction "-_1_PAD1") (pintype "bidirectional"))
    )
    (net (code "126") (name "/BUS-46") (class "Default")
      (node (ref "HEADER_3") (pin "25") (pinfunction "25_25") (pintype "passive"))
      (node (ref "P46") (pin "PAD1") (pinfunction "-_1_PAD1") (pintype "bidirectional"))
    )
    (net (code "127") (name "/BUS-47") (class "Default")
      (node (ref "HEADER_4") (pin "7") (pinfunction "7_7") (pintype "passive"))
      (node (ref "P47") (pin "PAD1") (pinfunction "-_1_PAD1") (pintype "bidirectional"))
    )
    (net (code "128") (name "/BUS-48") (class "Default")
      (node (ref "HEADER_4") (pin "25") (pinfunction "25_25") (pintype "passive"))
      (node (ref "P48") (pin "PAD1") (pinfunction "-_1_PAD1") (pintype "bidirectional"))
    )
    (net (code "129") (name "/BUS-49") (class "Default")
      (node (ref "HEADER_1") (pin "5") (pinfunction "5_5") (pintype "passive"))
      (node (ref "P49") (pin "PAD1") (pinfunction "-_1_PAD1") (pintype "bidirectional"))
    )
    (net (code "130") (name "/BUS-50") (class "Default")
      (node (ref "HEADER_1") (pin "23") (pinfunction "23_23") (pintype "passive"))
      (node (ref "P50") (pin "PAD1") (pinfunction "-_1_PAD1") (pintype "bidirectional"))
    )
    (net (code "131") (name "/BUS-51") (class "Default")
      (node (ref "HEADER_2") (pin "5") (pinfunction "5_5") (pintype "passive"))
      (node (ref "P51") (pin "PAD1") (pinfunction "-_1_PAD1") (pintype "bidirectional"))
    )
    (net (code "132") (name "/BUS-52") (class "Default")
      (node (ref "HEADER_2") (pin "23") (pinfunction "23_23") (pintype "passive"))
      (node (ref "P52") (pin "PAD1") (pinfunction "-_1_PAD1") (pintype "bidirectional"))
    )
    (net (code "133") (name "/BUS-53") (class "Default")
      (node (ref "HEADER_3") (pin "5") (pinfunction "5_5") (pintype "passive"))
      (node (ref "P53") (pin "PAD1") (pinfunction "-_1_PAD1") (pintype "bidirectional"))
    )
    (net (code "134") (name "/BUS-54") (class "Default")
      (node (ref "HEADER_3") (pin "23") (pinfunction "23_23") (pintype "passive"))
      (node (ref "P54") (pin "PAD1") (pinfunction "-_1_PAD1") (pintype "bidirectional"))
    )
    (net (code "135") (name "/BUS-55") (class "Default")
      (node (ref "HEADER_4") (pin "5") (pinfunction "5_5") (pintype "passive"))
      (node (ref "P55") (pin "PAD1") (pinfunction "-_1_PAD1") (pintype "bidirectional"))
    )
    (net (code "136") (name "/BUS-56") (class "Default")
      (node (ref "HEADER_4") (pin "23") (pinfunction "23_23") (pintype "passive"))
      (node (ref "P56") (pin "PAD1") (pinfunction "-_1_PAD1") (pintype "bidirectional"))
    )
    (net (code "137") (name "/BUS-57") (class "Default")
      (node (ref "HEADER_1") (pin "3") (pinfunction "3_3") (pintype "passive"))
      (node (ref "P57") (pin "PAD1") (pinfunction "-_1_PAD1") (pintype "bidirectional"))
    )
    (net (code "138") (name "/BUS-58") (class "Default")
      (node (ref "HEADER_1") (pin "21") (pinfunction "21_21") (pintype "passive"))
      (node (ref "P58") (pin "PAD1") (pinfunction "-_1_PAD1") (pintype "bidirectional"))
    )
    (net (code "139") (name "/BUS-59") (class "Default")
      (node (ref "HEADER_2") (pin "3") (pinfunction "3_3") (pintype "passive"))
      (node (ref "P59") (pin "PAD1") (pinfunction "-_1_PAD1") (pintype "bidirectional"))
    )
    (net (code "140") (name "/BUS-60") (class "Default")
      (node (ref "HEADER_2") (pin "21") (pinfunction "21_21") (pintype "passive"))
      (node (ref "P60") (pin "PAD1") (pinfunction "-_1_PAD1") (pintype "bidirectional"))
    )
    (net (code "141") (name "/BUS-61") (class "Default")
      (node (ref "HEADER_3") (pin "3") (pinfunction "3_3") (pintype "passive"))
      (node (ref "P61") (pin "PAD1") (pinfunction "-_1_PAD1") (pintype "bidirectional"))
    )
    (net (code "142") (name "/BUS-62") (class "Default")
      (node (ref "HEADER_3") (pin "21") (pinfunction "21_21") (pintype "passive"))
      (node (ref "P62") (pin "PAD1") (pinfunction "-_1_PAD1") (pintype "bidirectional"))
    )
    (net (code "143") (name "/BUS-63") (class "Default")
      (node (ref "HEADER_4") (pin "3") (pinfunction "3_3") (pintype "passive"))
      (node (ref "P63") (pin "PAD1") (pinfunction "-_1_PAD1") (pintype "bidirectional"))
    )
    (net (code "144") (name "/BUS-64") (class "Default")
      (node (ref "HEADER_4") (pin "21") (pinfunction "21_21") (pintype "passive"))
      (node (ref "P64") (pin "PAD1") (pinfunction "-_1_PAD1") (pintype "bidirectional"))
    )
    (net (code "145") (name "/BUS-70") (class "Default")
      (node (ref "HEADER_3") (pin "19") (pinfunction "19_19") (pintype "passive"))
      (node (ref "P65") (pin "PAD1") (pinfunction "-_1_PAD1") (pintype "bidirectional"))
      (node (ref "P66") (pin "PAD1") (pinfunction "-_1_PAD1") (pintype "bidirectional"))
      (node (ref "P67") (pin "PAD1") (pinfunction "-_1_PAD1") (pintype "bidirectional"))
      (node (ref "P68") (pin "PAD1") (pinfunction "-_1_PAD1") (pintype "bidirectional"))
      (node (ref "P69") (pin "PAD1") (pinfunction "-_1_PAD1") (pintype "bidirectional"))
      (node (ref "P70") (pin "PAD1") (pinfunction "-_1_PAD1") (pintype "bidirectional"))
      (node (ref "P71") (pin "PAD1") (pinfunction "-_1_PAD1") (pintype "bidirectional"))
      (node (ref "P72") (pin "PAD1") (pinfunction "-_1_PAD1") (pintype "bidirectional"))
    )
    (net (code "147") (name "unconnected-(HEADER_1-Pad1)") (class "Default")
      (node (ref "HEADER_1") (pin "1") (pinfunction "1_1") (pintype "passive"))
    )
    (net (code "148") (name "unconnected-(HEADER_1-Pad2)") (class "Default")
      (node (ref "HEADER_1") (pin "2") (pinfunction "2_2") (pintype "passive"))
    )
    (net (code "149") (name "unconnected-(HEADER_1-Pad4)") (class "Default")
      (node (ref "HEADER_1") (pin "4") (pinfunction "4_4") (pintype "passive"))
    )
    (net (code "150") (name "unconnected-(HEADER_1-Pad6)") (class "Default")
      (node (ref "HEADER_1") (pin "6") (pinfunction "6_6") (pintype "passive"))
    )
    (net (code "151") (name "unconnected-(HEADER_1-Pad8)") (class "Default")
      (node (ref "HEADER_1") (pin "8") (pinfunction "8_8") (pintype "passive"))
    )
    (net (code "152") (name "unconnected-(HEADER_1-Pad10)") (class "Default")
      (node (ref "HEADER_1") (pin "10") (pinfunction "10_10") (pintype "passive"))
    )
    (net (code "153") (name "unconnected-(HEADER_1-Pad12)") (class "Default")
      (node (ref "HEADER_1") (pin "12") (pinfunction "12_12") (pintype "passive"))
    )
    (net (code "154") (name "unconnected-(HEADER_1-Pad14)") (class "Default")
      (node (ref "HEADER_1") (pin "14") (pinfunction "14_14") (pintype "passive"))
    )
    (net (code "155") (name "unconnected-(HEADER_1-Pad16)") (class "Default")
      (node (ref "HEADER_1") (pin "16") (pinfunction "16_16") (pintype "passive"))
    )
    (net (code "156") (name "unconnected-(HEADER_1-Pad18)") (class "Default")
      (node (ref "HEADER_1") (pin "18") (pinfunction "18_18") (pintype "passive"))
    )
    (net (code "157") (name "unconnected-(HEADER_1-Pad19)") (class "Default")
      (node (ref "HEADER_1") (pin "19") (pinfunction "19_19") (pintype "passive"))
    )
    (net (code "158") (name "unconnected-(HEADER_1-Pad20)") (class "Default")
      (node (ref "HEADER_1") (pin "20") (pinfunction "20_20") (pintype "passive"))
    )
    (net (code "159") (name "unconnected-(HEADER_1-Pad22)") (class "Default")
      (node (ref "HEADER_1") (pin "22") (pinfunction "22_22") (pintype "passive"))
    )
    (net (code "160") (name "unconnected-(HEADER_1-Pad24)") (class "Default")
      (node (ref "HEADER_1") (pin "24") (pinfunction "24_24") (pintype "passive"))
    )
    (net (code "161") (name "unconnected-(HEADER_1-Pad26)") (class "Default")
      (node (ref "HEADER_1") (pin "26") (pinfunction "26_26") (pintype "passive"))
    )
    (net (code "162") (name "unconnected-(HEADER_1-Pad28)") (class "Default")
      (node (ref "HEADER_1") (pin "28") (pinfunction "28_28") (pintype "passive"))
    )
    (net (code "163") (name "unconnected-(HEADER_1-Pad30)") (class "Default")
      (node (ref "HEADER_1") (pin "30") (pinfunction "30_30") (pintype "passive"))
    )
    (net (code "164") (name "unconnected-(HEADER_1-Pad32)") (class "Default")
      (node (ref "HEADER_1") (pin "32") (pinfunction "32_32") (pintype "passive"))
    )
    (net (code "165") (name "unconnected-(HEADER_1-Pad34)") (class "Default")
      (node (ref "HEADER_1") (pin "34") (pinfunction "34_34") (pintype "passive"))
    )
    (net (code "166") (name "unconnected-(HEADER_1-Pad36)") (class "Default")
      (node (ref "HEADER_1") (pin "36") (pinfunction "36_36") (pintype "passive"))
    )
    (net (code "167") (name "unconnected-(HEADER_2-Pad1)") (class "Default")
      (node (ref "HEADER_2") (pin "1") (pinfunction "1_1") (pintype "passive"))
    )
    (net (code "168") (name "unconnected-(HEADER_2-Pad19)") (class "Default")
      (node (ref "HEADER_2") (pin "19") (pinfunction "19_19") (pintype "passive"))
    )
    (net (code "169") (name "unconnected-(HEADER_3-Pad1)") (class "Default")
      (node (ref "HEADER_3") (pin "1") (pinfunction "1_1") (pintype "passive"))
    )
    (net (code "170") (name "unconnected-(HEADER_4-Pad1)") (class "Default")
      (node (ref "HEADER_4") (pin "1") (pinfunction "1_1") (pintype "passive"))
    )
    (net (code "171") (name "unconnected-(HEADER_4-Pad19)") (class "Default")
      (node (ref "HEADER_4") (pin "19") (pinfunction "19_19") (pintype "passive"))
    )
    (net (code "172") (name "unconnected-(P01-+_1-PadTIP1)") (class "Default")
      (node (ref "P01") (pin "TIP1") (pinfunction "+_1_TIP1") (pintype "bidirectional"))
    )
    (net (code "173") (name "unconnected-(P02-+_1-PadTIP1)") (class "Default")
      (node (ref "P02") (pin "TIP1") (pinfunction "+_1_TIP1") (pintype "bidirectional"))
    )
    (net (code "174") (name "unconnected-(P09-+_1-PadTIP1)") (class "Default")
      (node (ref "P09") (pin "TIP1") (pinfunction "+_1_TIP1") (pintype "bidirectional"))
    )
    (net (code "175") (name "unconnected-(P10-+_1-PadTIP1)") (class "Default")
      (node (ref "P10") (pin "TIP1") (pinfunction "+_1_TIP1") (pintype "bidirectional"))
    )
    (net (code "176") (name "unconnected-(P17-+_1-PadTIP1)") (class "Default")
      (node (ref "P17") (pin "TIP1") (pinfunction "+_1_TIP1") (pintype "bidirectional"))
    )
    (net (code "177") (name "unconnected-(P18-+_1-PadTIP1)") (class "Default")
      (node (ref "P18") (pin "TIP1") (pinfunction "+_1_TIP1") (pintype "bidirectional"))
    )
    (net (code "178") (name "unconnected-(P25-+_1-PadTIP1)") (class "Default")
      (node (ref "P25") (pin "TIP1") (pinfunction "+_1_TIP1") (pintype "bidirectional"))
    )
    (net (code "179") (name "unconnected-(P26-+_1-PadTIP1)") (class "Default")
      (node (ref "P26") (pin "TIP1") (pinfunction "+_1_TIP1") (pintype "bidirectional"))
    )
    (net (code "180") (name "unconnected-(P33-+_1-PadTIP1)") (class "Default")
      (node (ref "P33") (pin "TIP1") (pinfunction "+_1_TIP1") (pintype "bidirectional"))
    )
    (net (code "181") (name "unconnected-(P34-+_1-PadTIP1)") (class "Default")
      (node (ref "P34") (pin "TIP1") (pinfunction "+_1_TIP1") (pintype "bidirectional"))
    )
    (net (code "182") (name "unconnected-(P41-+_1-PadTIP1)") (class "Default")
      (node (ref "P41") (pin "TIP1") (pinfunction "+_1_TIP1") (pintype "bidirectional"))
    )
    (net (code "183") (name "unconnected-(P42-+_1-PadTIP1)") (class "Default")
      (node (ref "P42") (pin "TIP1") (pinfunction "+_1_TIP1") (pintype "bidirectional"))
    )
    (net (code "184") (name "unconnected-(P49-+_1-PadTIP1)") (class "Default")
      (node (ref "P49") (pin "TIP1") (pinfunction "+_1_TIP1") (pintype "bidirectional"))
    )
    (net (code "185") (name "unconnected-(P50-+_1-PadTIP1)") (class "Default")
      (node (ref "P50") (pin "TIP1") (pinfunction "+_1_TIP1") (pintype "bidirectional"))
    )
    (net (code "186") (name "unconnected-(P57-+_1-PadTIP1)") (class "Default")
      (node (ref "P57") (pin "TIP1") (pinfunction "+_1_TIP1") (pintype "bidirectional"))
    )
    (net (code "187") (name "unconnected-(P58-+_1-PadTIP1)") (class "Default")
      (node (ref "P58") (pin "TIP1") (pinfunction "+_1_TIP1") (pintype "bidirectional"))
    )
    (net (code "188") (name "unconnected-(P65-+_1-PadTIP1)") (class "Default")
      (node (ref "P65") (pin "TIP1") (pinfunction "+_1_TIP1") (pintype "bidirectional"))
    )
    (net (code "189") (name "unconnected-(P66-+_1-PadTIP1)") (class "Default")
      (node (ref "P66") (pin "TIP1") (pinfunction "+_1_TIP1") (pintype "bidirectional"))
    )
  )
)
